# Protection_Circuit_24V.net
KiCad netlist of a schematic drawn in Altium Designer
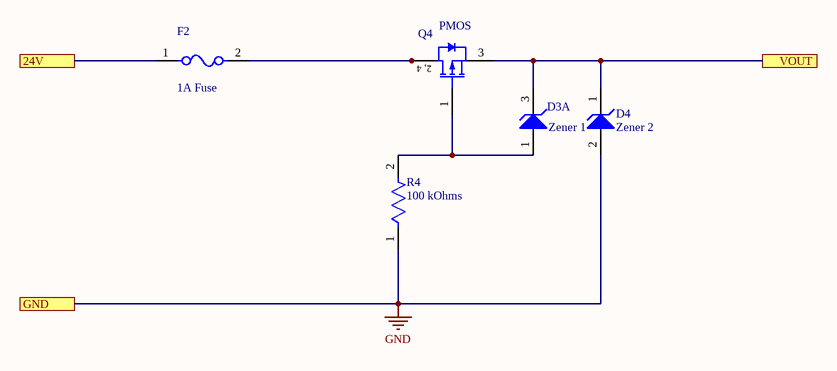
[diagram p0: Protection Circuit 24V.SchDoc]

(export (version "E")
  (design (tool "Eeschema 10.0.6"))
  (components
    (comp (ref "D3")
      (value "Zener 1")
      (footprint "ONSC-SOT-23-3-318-08_V")
      (description "Zener Voltage Regulator, 225 mW, 3-Pin SOT-23, Pb-Free, Tape and Reel")
      (fields (field (name "PARTNUMBER") "MMBZ5245BLT3G") (field (name "MANUFACTURER") "On Semiconductor"))
      (libsource (lib "Altium Content Vault") (part "ONSC-A1K3-3"))
    )
    (comp (ref "D4")
      (value "Zener 2")
      (footprint "ONSC-SMB-2-403A-03_H_V")
      (description "3 W Zener Voltage Regulator, 2-Pin SMB, Pb-Free, Tape and Reel")
      (fields (field (name "MANUFACTURER") "On Semiconductor") (field (name "PARTNUMBER") "1SMB5934BT3G"))
      (libsource (lib "Altium Content Vault") (part "ONSC-K1A2-2"))
    )
    (comp (ref "F2")
      (value "1A Fuse")
      (footprint "FP-0603SFS-MFG")
      (description "FUSE BOARD MOUNT 1A 32VDC 0603")
      (fields
        (field (name "OCTOPART") "https://octopart.com/0603sfs100f%2F32-2-littelfuse-74214378")
        (field (name "MANUFACTURER PART NUMBER") "0603SFS100F/32-2")
      )
      (libsource (lib "Altium Content Vault") (part "5bcf9b9f640e542cf0359d10258e979"))
    )
    (comp (ref "Q4")
      (value "PMOS")
      (footprint "FAIR-SOT223-4_V")
      (fields (field (name "MANUFACTURER") "Fairchild Semiconductor"))
      (libsource (lib "Altium Content Vault") (part "PEMOS-GDSD-4"))
    )
    (comp (ref "R4")
      (value "100 kOhms")
      (footprint "FP-CR0805-MFG")
      (description "Thick Film Chip Resistors 0805 100kΩ 0.125W 5% 200ppm/°C")
      (fields (field (name "TOLERANCE") "5%"))
      (libsource (lib "Altium Content Vault") (part "1029c3af85768c4190bb7ad29bc67b5"))
    )
  )
  (nets
    (net (code "1") (name "/24V") (class "Default")
      (node (ref "F2") (pin "1") (pinfunction "1_1") (pintype "passive"))
    )
    (net (code "2") (name "/VOUT") (class "Default")
      (node (ref "D3") (pin "3") (pinfunction "K_3") (pintype "passive"))
      (node (ref "D4") (pin "1") (pinfunction "K_1") (pintype "passive"))
      (node (ref "Q4") (pin "3") (pinfunction "SOURCE_3") (pintype "passive"))
    )
    (net (code "3") (name "GND") (class "Default")
      (node (ref "D4") (pin "2") (pinfunction "A_2") (pintype "passive"))
      (node (ref "R4") (pin "1") (pinfunction "1_1") (pintype "passive"))
    )
    (net (code "4") (name "Net-(D3A-A)") (class "Default")
      (node (ref "D3") (pin "1") (pinfunction "A_1") (pintype "passive"))
      (node (ref "Q4") (pin "1") (pinfunction "GATE_1") (pintype "passive"))
      (node (ref "R4") (pin "2") (pinfunction "2_2") (pintype "passive"))
    )
    (net (code "5") (name "Net-(F2-Pad2)") (class "Default")
      (node (ref "F2") (pin "2") (pinfunction "2_2") (pintype "passive"))
      (node (ref "Q4") (pin "2") (pinfunction "DRAIN_2") (pintype "passive"))
      (node (ref "Q4") (pin "4") (pinfunction "DRAIN_4") (pintype "passive"))
    )
  )
)
